# buttons.net
KiCad netlist of a schematic drawn in EAGLE
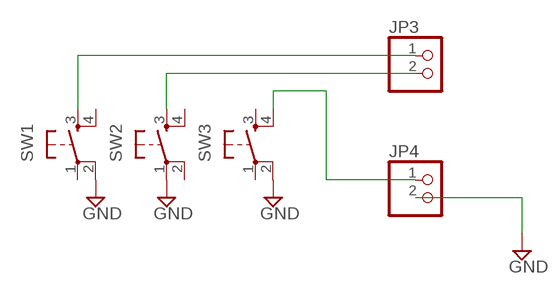
[diagram p0: schematic, sheet 1]

(export (version "E")
  (design (tool "Eeschema 10.0.6"))
  (components
    (comp (ref "JP3")
      (value "PINHD-1X2")
      (footprint "eagle-import:1X02")
      (libsource (lib "eagle-import") (part "PINHD-1X2"))
    )
    (comp (ref "JP4")
      (value "PINHD-1X2")
      (footprint "eagle-import:1X02")
      (libsource (lib "eagle-import") (part "PINHD-1X2"))
    )
    (comp (ref "SW1")
      (value "ALPS-4.2X3.2MM")
      (footprint "eagle-import:ALPS-4.2X3.2MM")
      (libsource (lib "eagle-import") (part "ALPS-4.2X3.2MM"))
    )
    (comp (ref "SW2")
      (value "ALPS-4.2X3.2MM")
      (footprint "eagle-import:ALPS-4.2X3.2MM")
      (libsource (lib "eagle-import") (part "ALPS-4.2X3.2MM"))
    )
    (comp (ref "SW3")
      (value "ALPS-4.2X3.2MM")
      (footprint "eagle-import:ALPS-4.2X3.2MM")
      (libsource (lib "eagle-import") (part "ALPS-4.2X3.2MM"))
    )
  )
  (nets
    (net (code "1") (name "GND") (class "Default")
      (node (ref "JP4") (pin "2") (pinfunction "2_2") (pintype "passive"))
      (node (ref "SW1") (pin "2") (pinfunction "P1_2") (pintype "passive"))
      (node (ref "SW2") (pin "1") (pinfunction "P_1") (pintype "passive"))
      (node (ref "SW3") (pin "2") (pinfunction "P1_2") (pintype "passive"))
    )
    (net (code "2") (name "Net-(SW1-S)") (class "Default")
      (node (ref "JP3") (pin "1") (pinfunction "1_1") (pintype "passive"))
      (node (ref "SW1") (pin "3") (pinfunction "S_3") (pintype "passive"))
    )
    (net (code "3") (name "Net-(SW2-S)") (class "Default")
      (node (ref "JP3") (pin "2") (pinfunction "2_2") (pintype "passive"))
      (node (ref "SW2") (pin "3") (pinfunction "S_3") (pintype "passive"))
    )
    (net (code "4") (name "Net-(SW3-S1)") (class "Default")
      (node (ref "JP4") (pin "1") (pinfunction "1_1") (pintype "passive"))
      (node (ref "SW3") (pin "4") (pinfunction "S1_4") (pintype "passive"))
    )
    (net (code "5") (name "unconnected-(SW1-P-Pad1)") (class "Default")
      (node (ref "SW1") (pin "1") (pinfunction "P_1") (pintype "passive"))
    )
    (net (code "6") (name "unconnected-(SW1-S1-Pad4)") (class "Default")
      (node (ref "SW1") (pin "4") (pinfunction "S1_4") (pintype "passive"))
    )
    (net (code "7") (name "unconnected-(SW2-P1-Pad2)") (class "Default")
      (node (ref "SW2") (pin "2") (pinfunction "P1_2") (pintype "passive"))
    )
    (net (code "8") (name "unconnected-(SW2-S1-Pad4)") (class "Default")
      (node (ref "SW2") (pin "4") (pinfunction "S1_4") (pintype "passive"))
    )
    (net (code "9") (name "unconnected-(SW3-P-Pad1)") (class "Default")
      (node (ref "SW3") (pin "1") (pinfunction "P_1") (pintype "passive"))
    )
    (net (code "10") (name "unconnected-(SW3-S-Pad3)") (class "Default")
      (node (ref "SW3") (pin "3") (pinfunction "S_3") (pintype "passive"))
    )
  )
)
